# renumbered.net
KiCad netlist of a schematic drawn in EAGLE
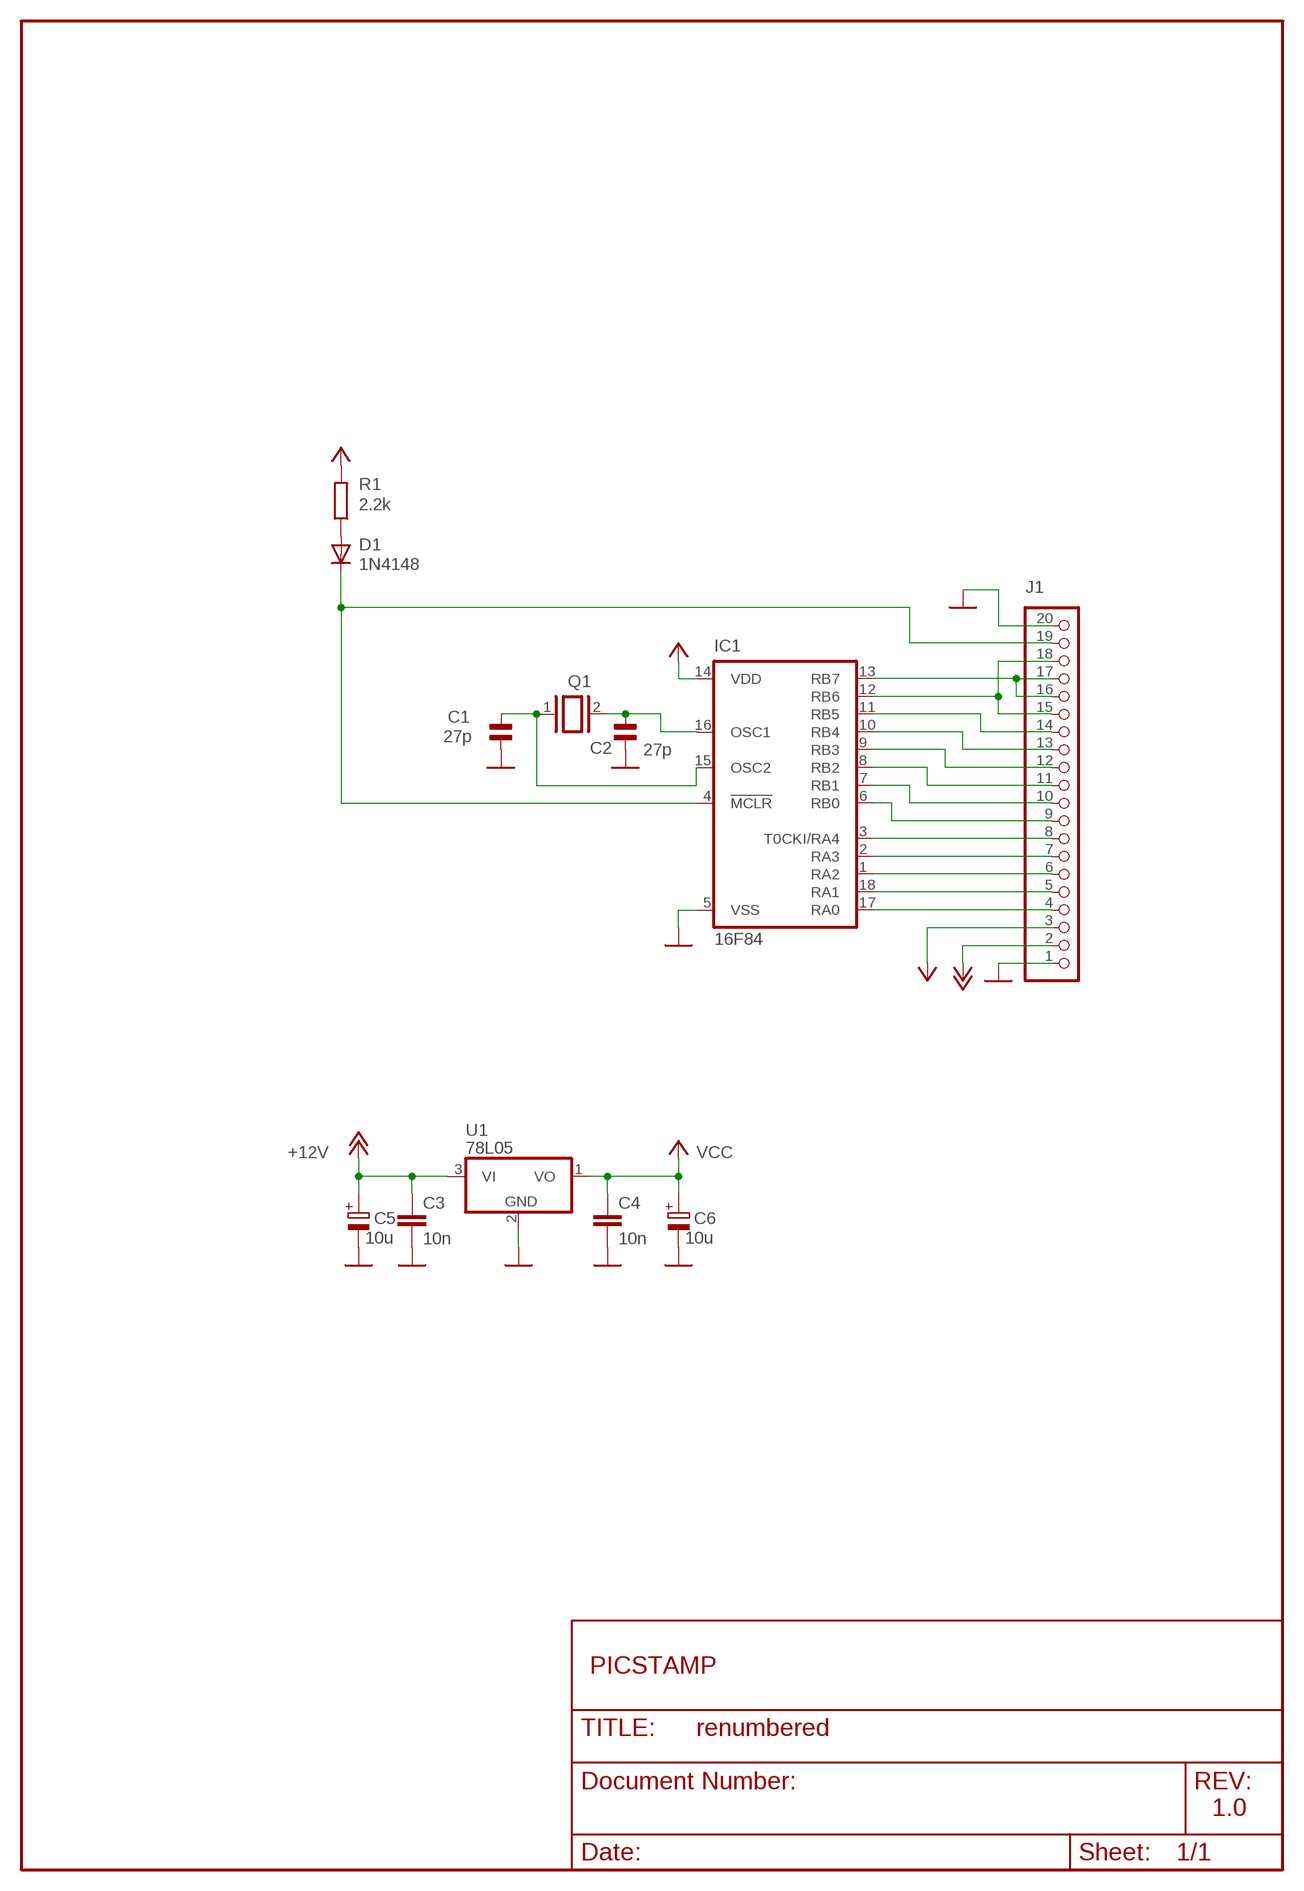
[diagram p0: schematic, sheet 1]

(export (version "E")
  (design (tool "Eeschema 10.0.6"))
  (components
    (comp (ref "C1")
      (value "27p")
      (footprint "eagle-import:C2,5-2")
      (libsource (lib "eagle-import") (part "C2.5/2"))
    )
    (comp (ref "C2")
      (value "27p")
      (footprint "eagle-import:C2,5-2")
      (libsource (lib "eagle-import") (part "C2.5/2"))
    )
    (comp (ref "C3")
      (value "10n")
      (footprint "eagle-import:C025-025X050")
      (libsource (lib "eagle-import") (part "C-EU025-025X050"))
    )
    (comp (ref "C4")
      (value "10n")
      (footprint "eagle-import:C025-025X050")
      (libsource (lib "eagle-import") (part "C-EU025-025X050"))
    )
    (comp (ref "C5")
      (value "10u")
      (footprint "eagle-import:E2,5-6")
      (libsource (lib "eagle-import") (part "E2,5-6"))
    )
    (comp (ref "C6")
      (value "10u")
      (footprint "eagle-import:E2,5-6")
      (libsource (lib "eagle-import") (part "E2,5-6"))
    )
    (comp (ref "D1")
      (value "1N4148")
      (footprint "eagle-import:DO35-10")
      (libsource (lib "eagle-import") (part "1N4148?"))
    )
    (comp (ref "IC1")
      (value "16F84")
      (footprint "eagle-import:DIL18")
      (libsource (lib "eagle-import") (part "PIC16F8P4A"))
    )
    (comp (ref "J1")
      (value "PINHD-1X20")
      (footprint "eagle-import:1X20")
      (libsource (lib "eagle-import") (part "PINHD-1X20"))
    )
    (comp (ref "Q1")
      (value "XTAL/S")
      (footprint "eagle-import:QS")
      (libsource (lib "eagle-import") (part "XTAL/S"))
    )
    (comp (ref "R1")
      (value "2.2k")
      (footprint "eagle-import:0207_10")
      (libsource (lib "eagle-import") (part "R-EU_0207/10"))
    )
    (comp (ref "U1")
      (value "78L05")
      (footprint "eagle-import:TO92")
      (libsource (lib "eagle-import") (part "78LXXZ"))
    )
  )
  (nets
    (net (code "1") (name "+12V") (class "Default")
      (node (ref "C3") (pin "2") (pinfunction "2_2") (pintype "passive"))
      (node (ref "C5") (pin "+") (pinfunction "+_+") (pintype "passive"))
      (node (ref "J1") (pin "2") (pinfunction "2_2") (pintype "passive"))
      (node (ref "U1") (pin "3") (pinfunction "VI_3") (pintype "input"))
    )
    (net (code "2") (name "GND") (class "Default")
      (node (ref "C1") (pin "1") (pinfunction "1_1") (pintype "passive"))
      (node (ref "C2") (pin "1") (pinfunction "1_1") (pintype "passive"))
      (node (ref "C3") (pin "1") (pinfunction "1_1") (pintype "passive"))
      (node (ref "C4") (pin "1") (pinfunction "1_1") (pintype "passive"))
      (node (ref "C5") (pin "-") (pinfunction "-_-") (pintype "passive"))
      (node (ref "C6") (pin "-") (pinfunction "-_-") (pintype "passive"))
      (node (ref "IC1") (pin "5") (pinfunction "VSS_5") (pintype "power_in"))
      (node (ref "J1") (pin "1") (pinfunction "1_1") (pintype "passive"))
      (node (ref "J1") (pin "20") (pinfunction "20_20") (pintype "passive"))
      (node (ref "U1") (pin "2") (pinfunction "GND_2") (pintype "passive"))
    )
    (net (code "3") (name "Net-(D1-C)") (class "Default")
      (node (ref "D1") (pin "K") (pinfunction "C_K") (pintype "passive"))
      (node (ref "IC1") (pin "4") (pinfunction "~{MCLR}_4") (pintype "input"))
      (node (ref "J1") (pin "19") (pinfunction "19_19") (pintype "passive"))
    )
    (net (code "4") (name "Net-(D1-PadA)") (class "Default")
      (node (ref "D1") (pin "A") (pinfunction "A_A") (pintype "passive"))
      (node (ref "R1") (pin "1") (pinfunction "1_1") (pintype "passive"))
    )
    (net (code "5") (name "Net-(IC1-OSC1)") (class "Default")
      (node (ref "C2") (pin "2") (pinfunction "2_2") (pintype "passive"))
      (node (ref "IC1") (pin "16") (pinfunction "OSC1_16") (pintype "input"))
      (node (ref "Q1") (pin "2") (pinfunction "2_2") (pintype "passive"))
    )
    (net (code "6") (name "Net-(IC1-OSC2)") (class "Default")
      (node (ref "C1") (pin "2") (pinfunction "2_2") (pintype "passive"))
      (node (ref "IC1") (pin "15") (pinfunction "OSC2_15") (pintype "output"))
      (node (ref "Q1") (pin "1") (pinfunction "1_1") (pintype "passive"))
    )
    (net (code "7") (name "Net-(IC1-RA0)") (class "Default")
      (node (ref "IC1") (pin "17") (pinfunction "RA0_17") (pintype "bidirectional"))
      (node (ref "J1") (pin "4") (pinfunction "4_4") (pintype "passive"))
    )
    (net (code "8") (name "Net-(IC1-RA1)") (class "Default")
      (node (ref "IC1") (pin "18") (pinfunction "RA1_18") (pintype "bidirectional"))
      (node (ref "J1") (pin "5") (pinfunction "5_5") (pintype "passive"))
    )
    (net (code "9") (name "Net-(IC1-RA2)") (class "Default")
      (node (ref "IC1") (pin "1") (pinfunction "RA2_1") (pintype "bidirectional"))
      (node (ref "J1") (pin "6") (pinfunction "6_6") (pintype "passive"))
    )
    (net (code "10") (name "Net-(IC1-RA3)") (class "Default")
      (node (ref "IC1") (pin "2") (pinfunction "RA3_2") (pintype "bidirectional"))
      (node (ref "J1") (pin "7") (pinfunction "7_7") (pintype "passive"))
    )
    (net (code "11") (name "Net-(IC1-RB0)") (class "Default")
      (node (ref "IC1") (pin "6") (pinfunction "RB0_6") (pintype "bidirectional"))
      (node (ref "J1") (pin "9") (pinfunction "9_9") (pintype "passive"))
    )
    (net (code "12") (name "Net-(IC1-RB1)") (class "Default")
      (node (ref "IC1") (pin "7") (pinfunction "RB1_7") (pintype "bidirectional"))
      (node (ref "J1") (pin "10") (pinfunction "10_10") (pintype "passive"))
    )
    (net (code "13") (name "Net-(IC1-RB2)") (class "Default")
      (node (ref "IC1") (pin "8") (pinfunction "RB2_8") (pintype "bidirectional"))
      (node (ref "J1") (pin "11") (pinfunction "11_11") (pintype "passive"))
    )
    (net (code "14") (name "Net-(IC1-RB3)") (class "Default")
      (node (ref "IC1") (pin "9") (pinfunction "RB3_9") (pintype "bidirectional"))
      (node (ref "J1") (pin "12") (pinfunction "12_12") (pintype "passive"))
    )
    (net (code "15") (name "Net-(IC1-RB4)") (class "Default")
      (node (ref "IC1") (pin "10") (pinfunction "RB4_10") (pintype "bidirectional"))
      (node (ref "J1") (pin "13") (pinfunction "13_13") (pintype "passive"))
    )
    (net (code "16") (name "Net-(IC1-RB5)") (class "Default")
      (node (ref "IC1") (pin "11") (pinfunction "RB5_11") (pintype "bidirectional"))
      (node (ref "J1") (pin "14") (pinfunction "14_14") (pintype "passive"))
    )
    (net (code "17") (name "Net-(IC1-RB6)") (class "Default")
      (node (ref "IC1") (pin "12") (pinfunction "RB6_12") (pintype "bidirectional"))
      (node (ref "J1") (pin "15") (pinfunction "15_15") (pintype "passive"))
      (node (ref "J1") (pin "18") (pinfunction "18_18") (pintype "passive"))
    )
    (net (code "18") (name "Net-(IC1-RB7)") (class "Default")
      (node (ref "IC1") (pin "13") (pinfunction "RB7_13") (pintype "bidirectional"))
      (node (ref "J1") (pin "16") (pinfunction "16_16") (pintype "passive"))
      (node (ref "J1") (pin "17") (pinfunction "17_17") (pintype "passive"))
    )
    (net (code "19") (name "Net-(IC1-T0CKI{slash}RA4)") (class "Default")
      (node (ref "IC1") (pin "3") (pinfunction "T0CKI/RA4_3") (pintype "bidirectional"))
      (node (ref "J1") (pin "8") (pinfunction "8_8") (pintype "passive"))
    )
    (net (code "20") (name "VCC") (class "Default")
      (node (ref "C4") (pin "2") (pinfunction "2_2") (pintype "passive"))
      (node (ref "C6") (pin "+") (pinfunction "+_+") (pintype "passive"))
      (node (ref "IC1") (pin "14") (pinfunction "VDD_14") (pintype "power_in"))
      (node (ref "J1") (pin "3") (pinfunction "3_3") (pintype "passive"))
      (node (ref "R1") (pin "2") (pinfunction "2_2") (pintype "passive"))
      (node (ref "U1") (pin "1") (pinfunction "VO_1") (pintype "output"))
    )
  )
)
